# ATmega324PB_Xplained_Pro_dual_input_powe.net
KiCad netlist of a schematic drawn in Altium Designer
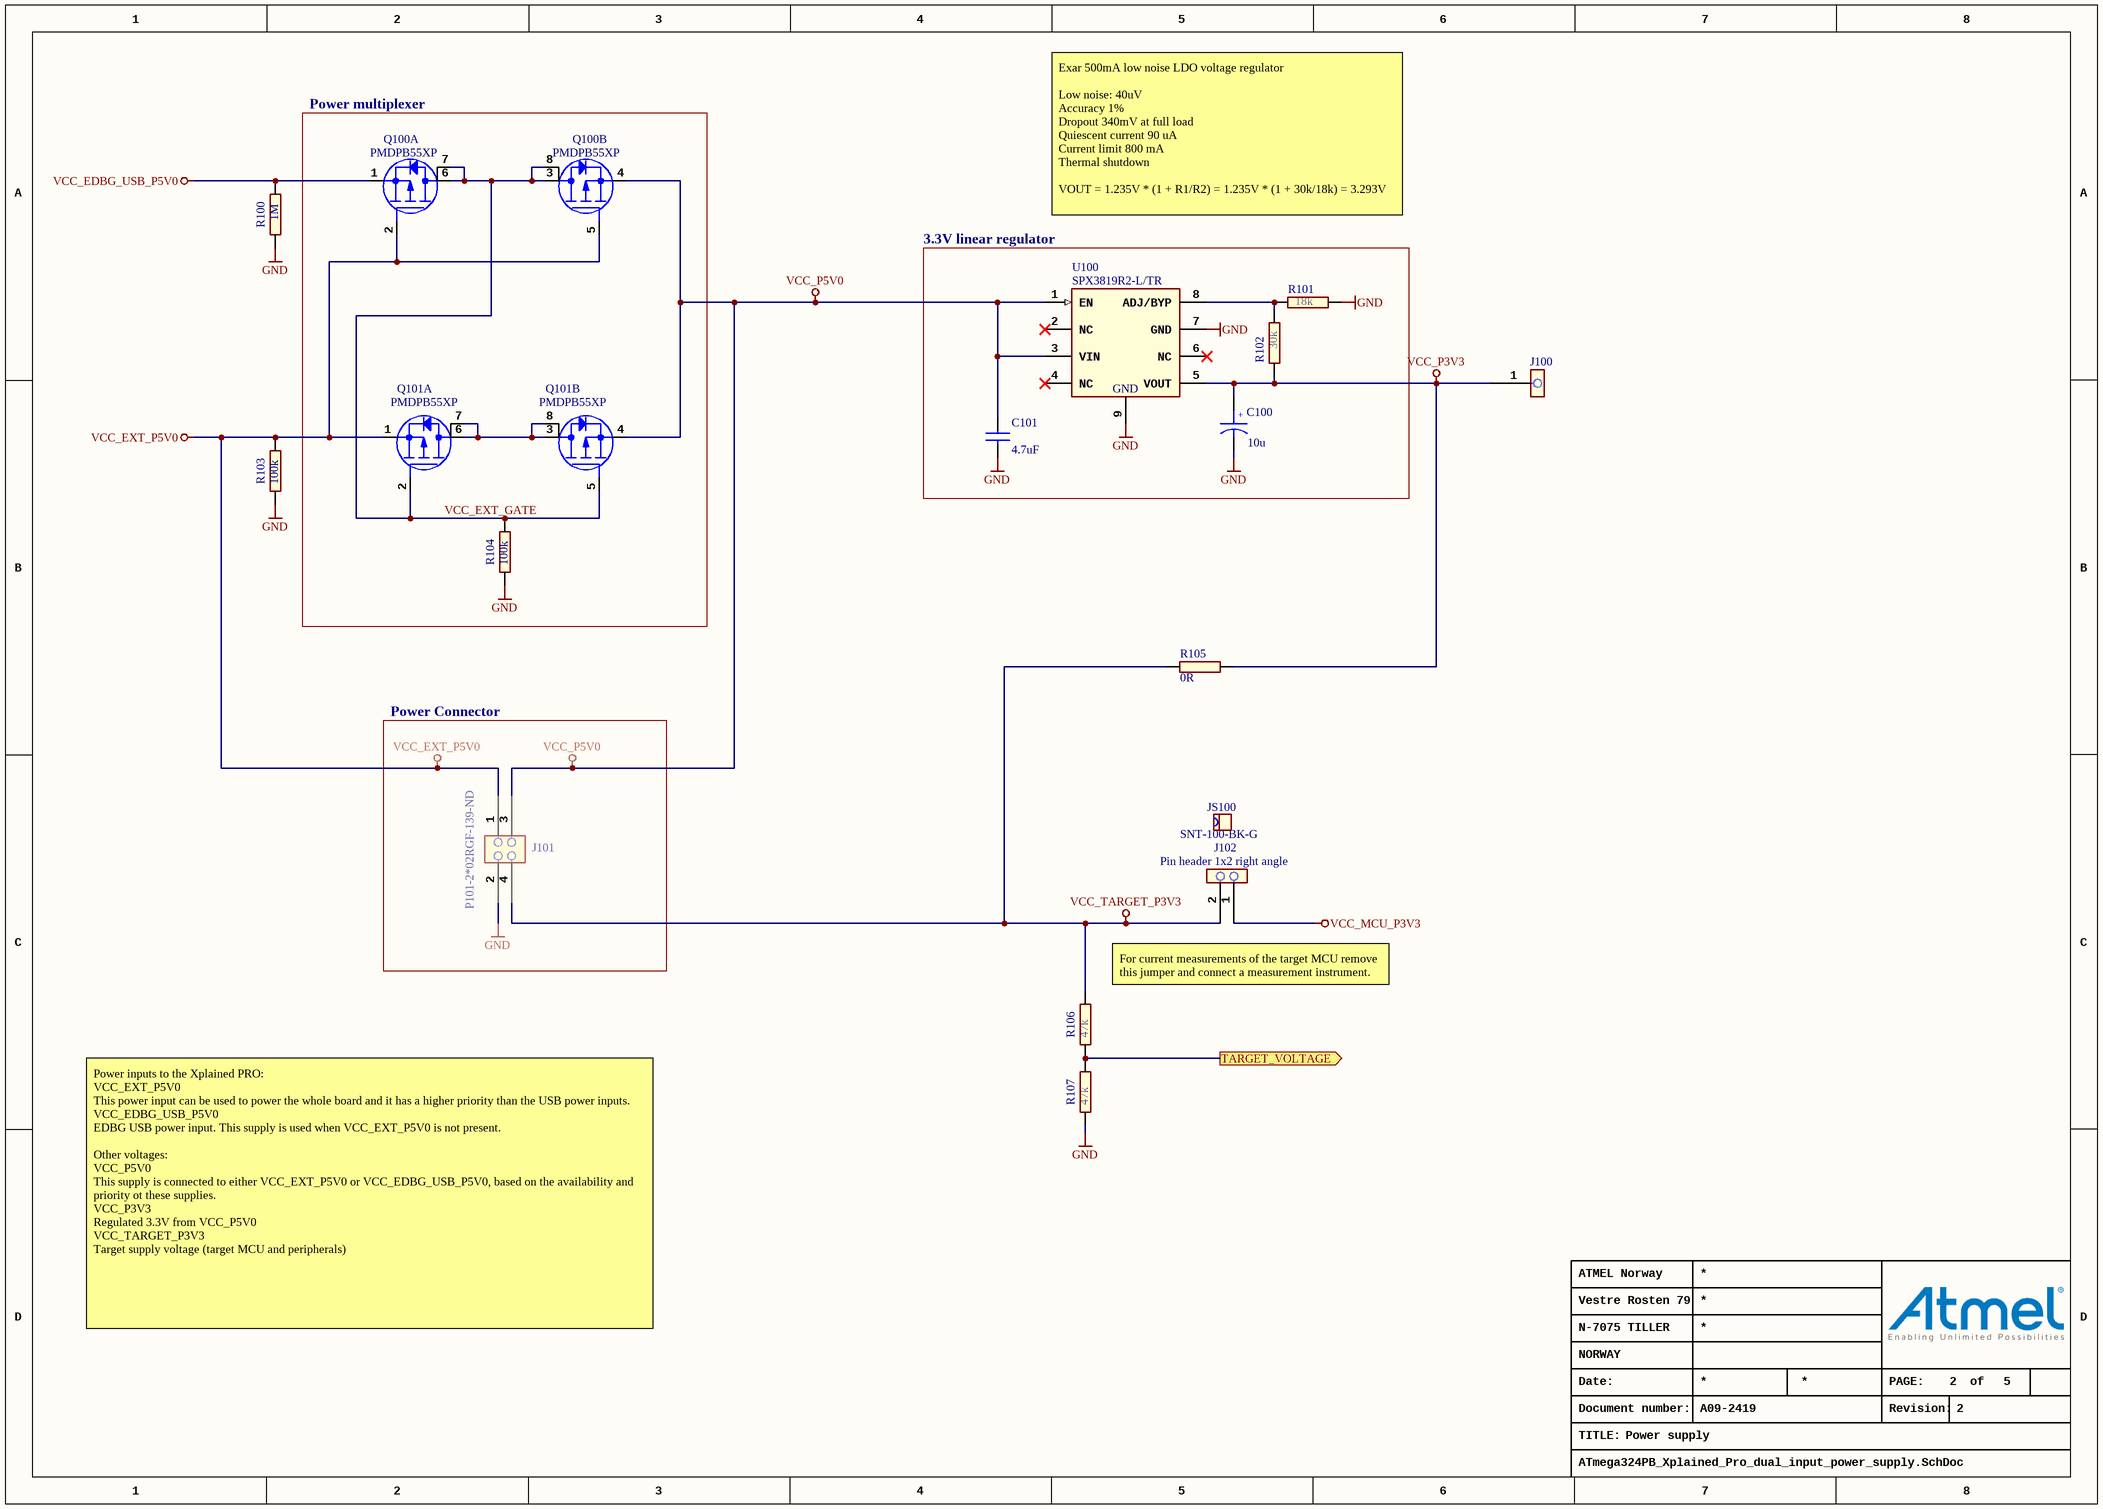
[diagram p0: ATmega324PB_Xplained_Pro_dual_input_power_supply.SchDoc]

(export (version "E")
  (design (tool "Eeschema 10.0.6"))
  (components
    (comp (ref "C100")
      (value "10u")
      (footprint "AP1-00036")
      (description "SMD tantalum capacitor, ESR = 1.7, 3216-18 (EIA) 1206,")
      (fields (field (name "TOLERANCE") "+-10%") (field (name "MANUFACTURER") "vishay"))
      (libsource (lib "AltiumDbLib") (part "CAP-POL"))
    )
    (comp (ref "C101")
      (value "4.7uF")
      (footprint "AP1-00039")
      (description "Ceramic capacitor, SMD 0603, X5R, 10V, 10% (de31036)")
      (fields (field (name "TOLERANCE") "10%") (field (name "MANUFACTURER") "tdk"))
      (libsource (lib "AltiumDbLib") (part "CAP-NONPOL"))
    )
    (comp (ref "J100")
      (value "~")
      (footprint "AP8-00976")
      (description "1x1 pin header, 2.54mm pitch, Pin-in-Paste THM")
      (fields (field (name "MANUFACTURER") "SAMTEC") (field (name "MPN") "HMTSW-101-23-F-S-237"))
      (libsource (lib "AltiumDbLib") (part "HEADER 1x1"))
    )
    (comp (ref "J101")
      (value "P101-2*02RGF-139-ND")
      (footprint "AP8-00628")
      (description "Pin header, 2x2, Right Angle, 2.54mm, THT, Pin In Paste")
      (fields (field (name "MANUFACTURER") "Pro-data International Corp"))
      (libsource (lib "AltiumDbLib") (part "HEADER 2x2"))
    )
    (comp (ref "J102")
      (value "Pin header 1x2 right angle")
      (footprint "AP8-00367")
      (description "1x2 pin header, right angle, 2.54 mm pitch, through-hole")
      (fields (field (name "MANUFACTURER") "Pro-data International Corp") (field (name "MPN") "2213R-2G"))
      (libsource (lib "AltiumDbLib") (part "HEADER 1x2"))
    )
    (comp (ref "JS100")
      (value "SNT-100-BK-G")
      (footprint "AP8-00525")
      (description "Jumper cap for 2.54mm pinheader")
      (fields (field (name "MANUFACTURER") "SAMTEC"))
      (libsource (lib "AltiumDbLib") (part "JUMPER_CAP"))
    )
    (comp (ref "Q100")
      (value "PMDPB55XP")
      (footprint "AP5-00047")
      (description "Dual P-Channel MOSFET, -20V, RDS(ON) < 55 mOhm @-3.4A@-4.5V")
      (fields (field (name "MANUFACTURER") "NXP") (field (name "Comment") "Farnell order code: 2191806"))
      (libsource (lib "AltiumDbLib") (part "MOSFET_DUAL_P_S1G1D2S2G2D1D1D2"))
    )
    (comp (ref "Q101")
      (value "PMDPB55XP")
      (footprint "AP5-00047")
      (description "Dual P-Channel MOSFET, -20V, RDS(ON) < 55 mOhm @-3.4A@-4.5V")
      (fields (field (name "MANUFACTURER") "NXP") (field (name "Comment") "Farnell order code: 2191806"))
      (libsource (lib "AltiumDbLib") (part "MOSFET_DUAL_P_S1G1D2S2G2D1D1D2"))
    )
    (comp (ref "R100")
      (value "1M")
      (footprint "AP2-00000")
      (description "Thick film resistor, SMD 0402, 1/16W, 1%")
      (fields (field (name "TOLERANCE") "1 %"))
      (libsource (lib "") (part "R2_1"))
    )
    (comp (ref "R101")
      (value "18k")
      (footprint "AP2-00000")
      (description "Thick film resistor, SMD 0402, 1/16W, 1%")
      (fields (field (name "TOLERANCE") "1 %"))
      (libsource (lib "") (part "R2_2"))
    )
    (comp (ref "R102")
      (value "30k")
      (footprint "AP2-00000")
      (description "Thick film resistor, SMD 0402, 1/16W, 1%")
      (fields (field (name "TOLERANCE") "1 %"))
      (libsource (lib "") (part "R2_1"))
    )
    (comp (ref "R103")
      (value "100k")
      (footprint "AP2-00000")
      (description "Thick film resistor, SMD 0402, 1/16W, 1%")
      (fields (field (name "TOLERANCE") "1 %"))
      (libsource (lib "") (part "R2_1"))
    )
    (comp (ref "R104")
      (value "100k")
      (footprint "AP2-00000")
      (description "Thick film resistor, SMD 0402, 1/16W, 1%")
      (fields (field (name "TOLERANCE") "1 %"))
      (libsource (lib "") (part "R2_1"))
    )
    (comp (ref "R105")
      (value "0R")
      (footprint "AP2-00000")
      (description "RES 0.0 OHM 1/16W 0402 SMD")
      (fields (field (name "TOLERANCE") "1 %") (field (name "MANUFACTURER") "(n/a)"))
      (libsource (lib "") (part "R2_2"))
    )
    (comp (ref "R106")
      (value "47k")
      (footprint "AP2-00000")
      (description "Thick film resistor, SMD 0402, 1/16W, 1%")
      (fields (field (name "TOLERANCE") "1 %"))
      (libsource (lib "AltiumDbLib") (part "R2"))
    )
    (comp (ref "R107")
      (value "47k")
      (footprint "AP2-00000")
      (description "Thick film resistor, SMD 0402, 1/16W, 1%")
      (fields (field (name "TOLERANCE") "1 %"))
      (libsource (lib "AltiumDbLib") (part "R2"))
    )
    (comp (ref "U100")
      (value "SPX3819R2-L/TR")
      (footprint "AP6-00338")
      (description "500mA LDO, ADJ, low noise, 8-DFN package")
      (fields (field (name "TOLERANCE") "±1%") (field (name "MANUFACTURER") "Exar"))
      (libsource (lib "AltiumDbLib") (part "SPX3819R2-L"))
    )
  )
  (nets
    (net (code "1") (name "/TARGET_VOLTAGE") (class "Default")
      (node (ref "R106") (pin "1") (pinfunction "1_1") (pintype "passive"))
      (node (ref "R107") (pin "2") (pinfunction "2_2") (pintype "passive"))
    )
    (net (code "2") (name "/VCC_EXT_GATE") (class "Default")
      (node (ref "Q100") (pin "3") (pinfunction "D2_3") (pintype "passive"))
      (node (ref "Q100") (pin "6") (pinfunction "D1_6") (pintype "passive"))
      (node (ref "Q100") (pin "7") (pinfunction "D1_PAD_7") (pintype "passive"))
      (node (ref "Q100") (pin "8") (pinfunction "D2_PAD_8") (pintype "passive"))
      (node (ref "Q101") (pin "2") (pinfunction "G1_2") (pintype "passive"))
      (node (ref "Q101") (pin "5") (pinfunction "G2_5") (pintype "passive"))
      (node (ref "R104") (pin "2") (pinfunction "2_2") (pintype "passive"))
    )
    (net (code "3") (name "GND") (class "Default")
      (node (ref "C100") (pin "2") (pinfunction "2_2") (pintype "passive"))
      (node (ref "C101") (pin "2") (pinfunction "2_2") (pintype "passive"))
      (node (ref "J101") (pin "2") (pinfunction "2_2") (pintype "passive"))
      (node (ref "R100") (pin "1") (pinfunction "1_1") (pintype "passive"))
      (node (ref "R101") (pin "2") (pinfunction "2_2") (pintype "passive"))
      (node (ref "R103") (pin "1") (pinfunction "1_1") (pintype "passive"))
      (node (ref "R104") (pin "1") (pinfunction "1_1") (pintype "passive"))
      (node (ref "R107") (pin "1") (pinfunction "1_1") (pintype "passive"))
      (node (ref "U100") (pin "7") (pinfunction "GND_7") (pintype "power_in"))
      (node (ref "U100") (pin "9") (pinfunction "GND_9") (pintype "power_in"))
    )
    (net (code "4") (name "Net-(Q101A-D1)") (class "Default")
      (node (ref "Q101") (pin "3") (pinfunction "D2_3") (pintype "passive"))
      (node (ref "Q101") (pin "6") (pinfunction "D1_6") (pintype "passive"))
      (node (ref "Q101") (pin "7") (pinfunction "D1_PAD_7") (pintype "passive"))
      (node (ref "Q101") (pin "8") (pinfunction "D2_PAD_8") (pintype "passive"))
    )
    (net (code "5") (name "Net-(U100-ADJ{slash}BYP)") (class "Default")
      (node (ref "R101") (pin "1") (pinfunction "1_1") (pintype "passive"))
      (node (ref "R102") (pin "2") (pinfunction "2_2") (pintype "passive"))
      (node (ref "U100") (pin "8") (pinfunction "ADJ/BYP_8") (pintype "passive"))
    )
    (net (code "6") (name "VCC_EDBG_USB_P5V0") (class "Default")
      (node (ref "Q100") (pin "1") (pinfunction "S1_1") (pintype "passive"))
      (node (ref "R100") (pin "2") (pinfunction "2_2") (pintype "passive"))
    )
    (net (code "7") (name "VCC_EXT_P5V0") (class "Default")
      (node (ref "J101") (pin "1") (pinfunction "1_1") (pintype "passive"))
      (node (ref "Q100") (pin "2") (pinfunction "G1_2") (pintype "passive"))
      (node (ref "Q100") (pin "5") (pinfunction "G2_5") (pintype "passive"))
      (node (ref "Q101") (pin "1") (pinfunction "S1_1") (pintype "passive"))
      (node (ref "R103") (pin "2") (pinfunction "2_2") (pintype "passive"))
    )
    (net (code "8") (name "VCC_MCU_P3V3") (class "Default")
      (node (ref "J102") (pin "1") (pinfunction "1_1") (pintype "passive"))
    )
    (net (code "9") (name "VCC_P3V3") (class "Default")
      (node (ref "C100") (pin "1") (pinfunction "1_1") (pintype "passive"))
      (node (ref "J100") (pin "1") (pinfunction "1_1") (pintype "passive"))
      (node (ref "R102") (pin "1") (pinfunction "1_1") (pintype "passive"))
      (node (ref "R105") (pin "2") (pinfunction "2_2") (pintype "passive"))
      (node (ref "U100") (pin "5") (pinfunction "VOUT_5") (pintype "power_in"))
    )
    (net (code "10") (name "VCC_P5V0") (class "Default")
      (node (ref "C101") (pin "1") (pinfunction "1_1") (pintype "passive"))
      (node (ref "J101") (pin "3") (pinfunction "3_3") (pintype "passive"))
      (node (ref "Q100") (pin "4") (pinfunction "S2_4") (pintype "passive"))
      (node (ref "Q101") (pin "4") (pinfunction "S2_4") (pintype "passive"))
      (node (ref "U100") (pin "1") (pinfunction "EN_1") (pintype "input"))
      (node (ref "U100") (pin "3") (pinfunction "VIN_3") (pintype "power_in"))
    )
    (net (code "11") (name "VCC_TARGET_P3V3") (class "Default")
      (node (ref "J101") (pin "4") (pinfunction "4_4") (pintype "passive"))
      (node (ref "J102") (pin "2") (pinfunction "2_2") (pintype "passive"))
      (node (ref "R105") (pin "1") (pinfunction "1_1") (pintype "passive"))
      (node (ref "R106") (pin "2") (pinfunction "2_2") (pintype "passive"))
    )
    (net (code "12") (name "unconnected-(U100-NC-Pad2)") (class "Default")
      (node (ref "U100") (pin "2") (pinfunction "NC_2") (pintype "passive+no_connect"))
    )
    (net (code "13") (name "unconnected-(U100-NC-Pad4)") (class "Default")
      (node (ref "U100") (pin "4") (pinfunction "NC_4") (pintype "passive+no_connect"))
    )
    (net (code "14") (name "unconnected-(U100-NC-Pad6)") (class "Default")
      (node (ref "U100") (pin "6") (pinfunction "NC_6") (pintype "passive+no_connect"))
    )
  )
)
